# Transmitter.net
KiCad netlist of a schematic drawn in EAGLE
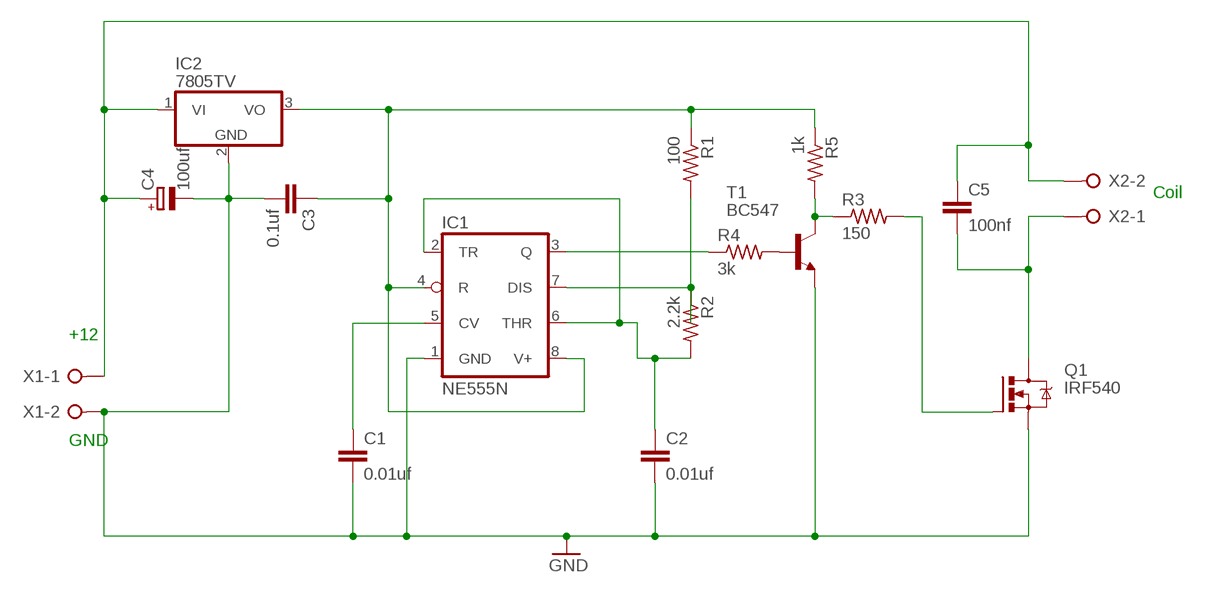
[diagram p0: schematic, sheet 1]

(export (version "E")
  (design (tool "Eeschema 10.0.6"))
  (components
    (comp (ref "C1")
      (value "0.01uf")
      (footprint "eagle-import:C025-030X050")
      (libsource (lib "eagle-import") (part "C-EU025-030X050"))
    )
    (comp (ref "C2")
      (value "0.01uf")
      (footprint "eagle-import:C025-030X050")
      (libsource (lib "eagle-import") (part "C-EU025-030X050"))
    )
    (comp (ref "C3")
      (value "0.1uf")
      (footprint "eagle-import:C025-030X050")
      (libsource (lib "eagle-import") (part "C-EU025-030X050"))
    )
    (comp (ref "C4")
      (value "100uf")
      (footprint "eagle-import:E2,5-6E")
      (libsource (lib "eagle-import") (part "CPOL-EUE2,5-6E"))
    )
    (comp (ref "C5")
      (value "100nf")
      (footprint "eagle-import:C102-064X133")
      (libsource (lib "eagle-import") (part "C-EU102-064X133"))
    )
    (comp (ref "IC1")
      (value "NE555N")
      (footprint "eagle-import:DIL08")
      (libsource (lib "eagle-import") (part "555NNE"))
    )
    (comp (ref "IC2")
      (value "7805TV")
      (footprint "eagle-import:TO220V")
      (libsource (lib "eagle-import") (part "78TV05"))
    )
    (comp (ref "Q1")
      (value "IRF540")
      (footprint "eagle-import:TO220BV")
      (libsource (lib "eagle-import") (part "IRF540"))
    )
    (comp (ref "R1")
      (value "100")
      (footprint "eagle-import:0207_10")
      (libsource (lib "eagle-import") (part "R-US_0207/10"))
    )
    (comp (ref "R2")
      (value "2.2k")
      (footprint "eagle-import:0207_10")
      (libsource (lib "eagle-import") (part "R-US_0207/10"))
    )
    (comp (ref "R3")
      (value "150")
      (footprint "eagle-import:0207_10")
      (libsource (lib "eagle-import") (part "R-US_0207/10"))
    )
    (comp (ref "R4")
      (value "3k")
      (footprint "eagle-import:0207_10")
      (libsource (lib "eagle-import") (part "R-US_0207/10"))
    )
    (comp (ref "R5")
      (value "1k")
      (footprint "eagle-import:0207_10")
      (libsource (lib "eagle-import") (part "R-US_0207/10"))
    )
    (comp (ref "T1")
      (value "BC547")
      (footprint "eagle-import:TO92")
      (libsource (lib "eagle-import") (part "BC547"))
    )
    (comp (ref "X1")
      (value "W237-02P")
      (footprint "eagle-import:W237-132")
      (libsource (lib "eagle-import") (part "W237-02P"))
    )
    (comp (ref "X2")
      (value "W237-02P")
      (footprint "eagle-import:W237-132")
      (libsource (lib "eagle-import") (part "W237-02P"))
    )
  )
  (nets
    (net (code "1") (name "GND") (class "Default")
      (node (ref "C1") (pin "2") (pinfunction "2_2") (pintype "passive"))
      (node (ref "C2") (pin "2") (pinfunction "2_2") (pintype "passive"))
      (node (ref "C3") (pin "2") (pinfunction "2_2") (pintype "passive"))
      (node (ref "C4") (pin "-") (pinfunction "-_-") (pintype "passive"))
      (node (ref "IC1") (pin "1") (pinfunction "GND_1") (pintype "power_in"))
      (node (ref "IC2") (pin "2") (pinfunction "GND_2") (pintype "passive"))
      (node (ref "Q1") (pin "S") (pinfunction "S_S") (pintype "passive"))
      (node (ref "T1") (pin "1") (pinfunction "E_1") (pintype "passive"))
      (node (ref "X1") (pin "2") (pinfunction "KL_2") (pintype "passive"))
    )
    (net (code "2") (name "Net-(IC1-CV)") (class "Default")
      (node (ref "C1") (pin "1") (pinfunction "1_1") (pintype "passive"))
      (node (ref "IC1") (pin "5") (pinfunction "CV_5") (pintype "input"))
    )
    (net (code "3") (name "Net-(IC1-DIS)") (class "Default")
      (node (ref "IC1") (pin "7") (pinfunction "DIS_7") (pintype "input"))
      (node (ref "R1") (pin "2") (pinfunction "2_2") (pintype "passive"))
      (node (ref "R2") (pin "1") (pinfunction "1_1") (pintype "passive"))
    )
    (net (code "4") (name "Net-(IC1-Q)") (class "Default")
      (node (ref "IC1") (pin "3") (pinfunction "Q_3") (pintype "output"))
      (node (ref "R4") (pin "1") (pinfunction "1_1") (pintype "passive"))
    )
    (net (code "5") (name "Net-(IC1-R)") (class "Default")
      (node (ref "C3") (pin "1") (pinfunction "1_1") (pintype "passive"))
      (node (ref "IC1") (pin "4") (pinfunction "R_4") (pintype "input"))
      (node (ref "IC1") (pin "8") (pinfunction "V+_8") (pintype "power_in"))
      (node (ref "IC2") (pin "3") (pinfunction "VO_3") (pintype "passive"))
      (node (ref "R1") (pin "1") (pinfunction "1_1") (pintype "passive"))
      (node (ref "R5") (pin "1") (pinfunction "1_1") (pintype "passive"))
    )
    (net (code "6") (name "Net-(IC1-THR)") (class "Default")
      (node (ref "C2") (pin "1") (pinfunction "1_1") (pintype "passive"))
      (node (ref "IC1") (pin "2") (pinfunction "TR_2") (pintype "input"))
      (node (ref "IC1") (pin "6") (pinfunction "THR_6") (pintype "input"))
      (node (ref "R2") (pin "2") (pinfunction "2_2") (pintype "passive"))
    )
    (net (code "7") (name "Net-(IC2-VI)") (class "Default")
      (node (ref "C4") (pin "+") (pinfunction "+_+") (pintype "passive"))
      (node (ref "C5") (pin "1") (pinfunction "1_1") (pintype "passive"))
      (node (ref "IC2") (pin "1") (pinfunction "VI_1") (pintype "input"))
      (node (ref "X1") (pin "1") (pinfunction "KL_1") (pintype "passive"))
      (node (ref "X2") (pin "2") (pinfunction "KL_2") (pintype "passive"))
    )
    (net (code "8") (name "Net-(Q1-PadG)") (class "Default")
      (node (ref "Q1") (pin "G") (pinfunction "G_G") (pintype "passive"))
      (node (ref "R3") (pin "2") (pinfunction "2_2") (pintype "passive"))
    )
    (net (code "9") (name "Net-(T1-B)") (class "Default")
      (node (ref "R4") (pin "2") (pinfunction "2_2") (pintype "passive"))
      (node (ref "T1") (pin "2") (pinfunction "B_2") (pintype "passive"))
    )
    (net (code "10") (name "Net-(T1-C)") (class "Default")
      (node (ref "R3") (pin "1") (pinfunction "1_1") (pintype "passive"))
      (node (ref "R5") (pin "2") (pinfunction "2_2") (pintype "passive"))
      (node (ref "T1") (pin "3") (pinfunction "C_3") (pintype "passive"))
    )
    (net (code "11") (name "Net-(X2A-KL)") (class "Default")
      (node (ref "C5") (pin "2") (pinfunction "2_2") (pintype "passive"))
      (node (ref "Q1") (pin "D") (pinfunction "D_D") (pintype "passive"))
      (node (ref "X2") (pin "1") (pinfunction "KL_1") (pintype "passive"))
    )
  )
)
